# RF.net
KiCad netlist of a schematic drawn in Altium Designer
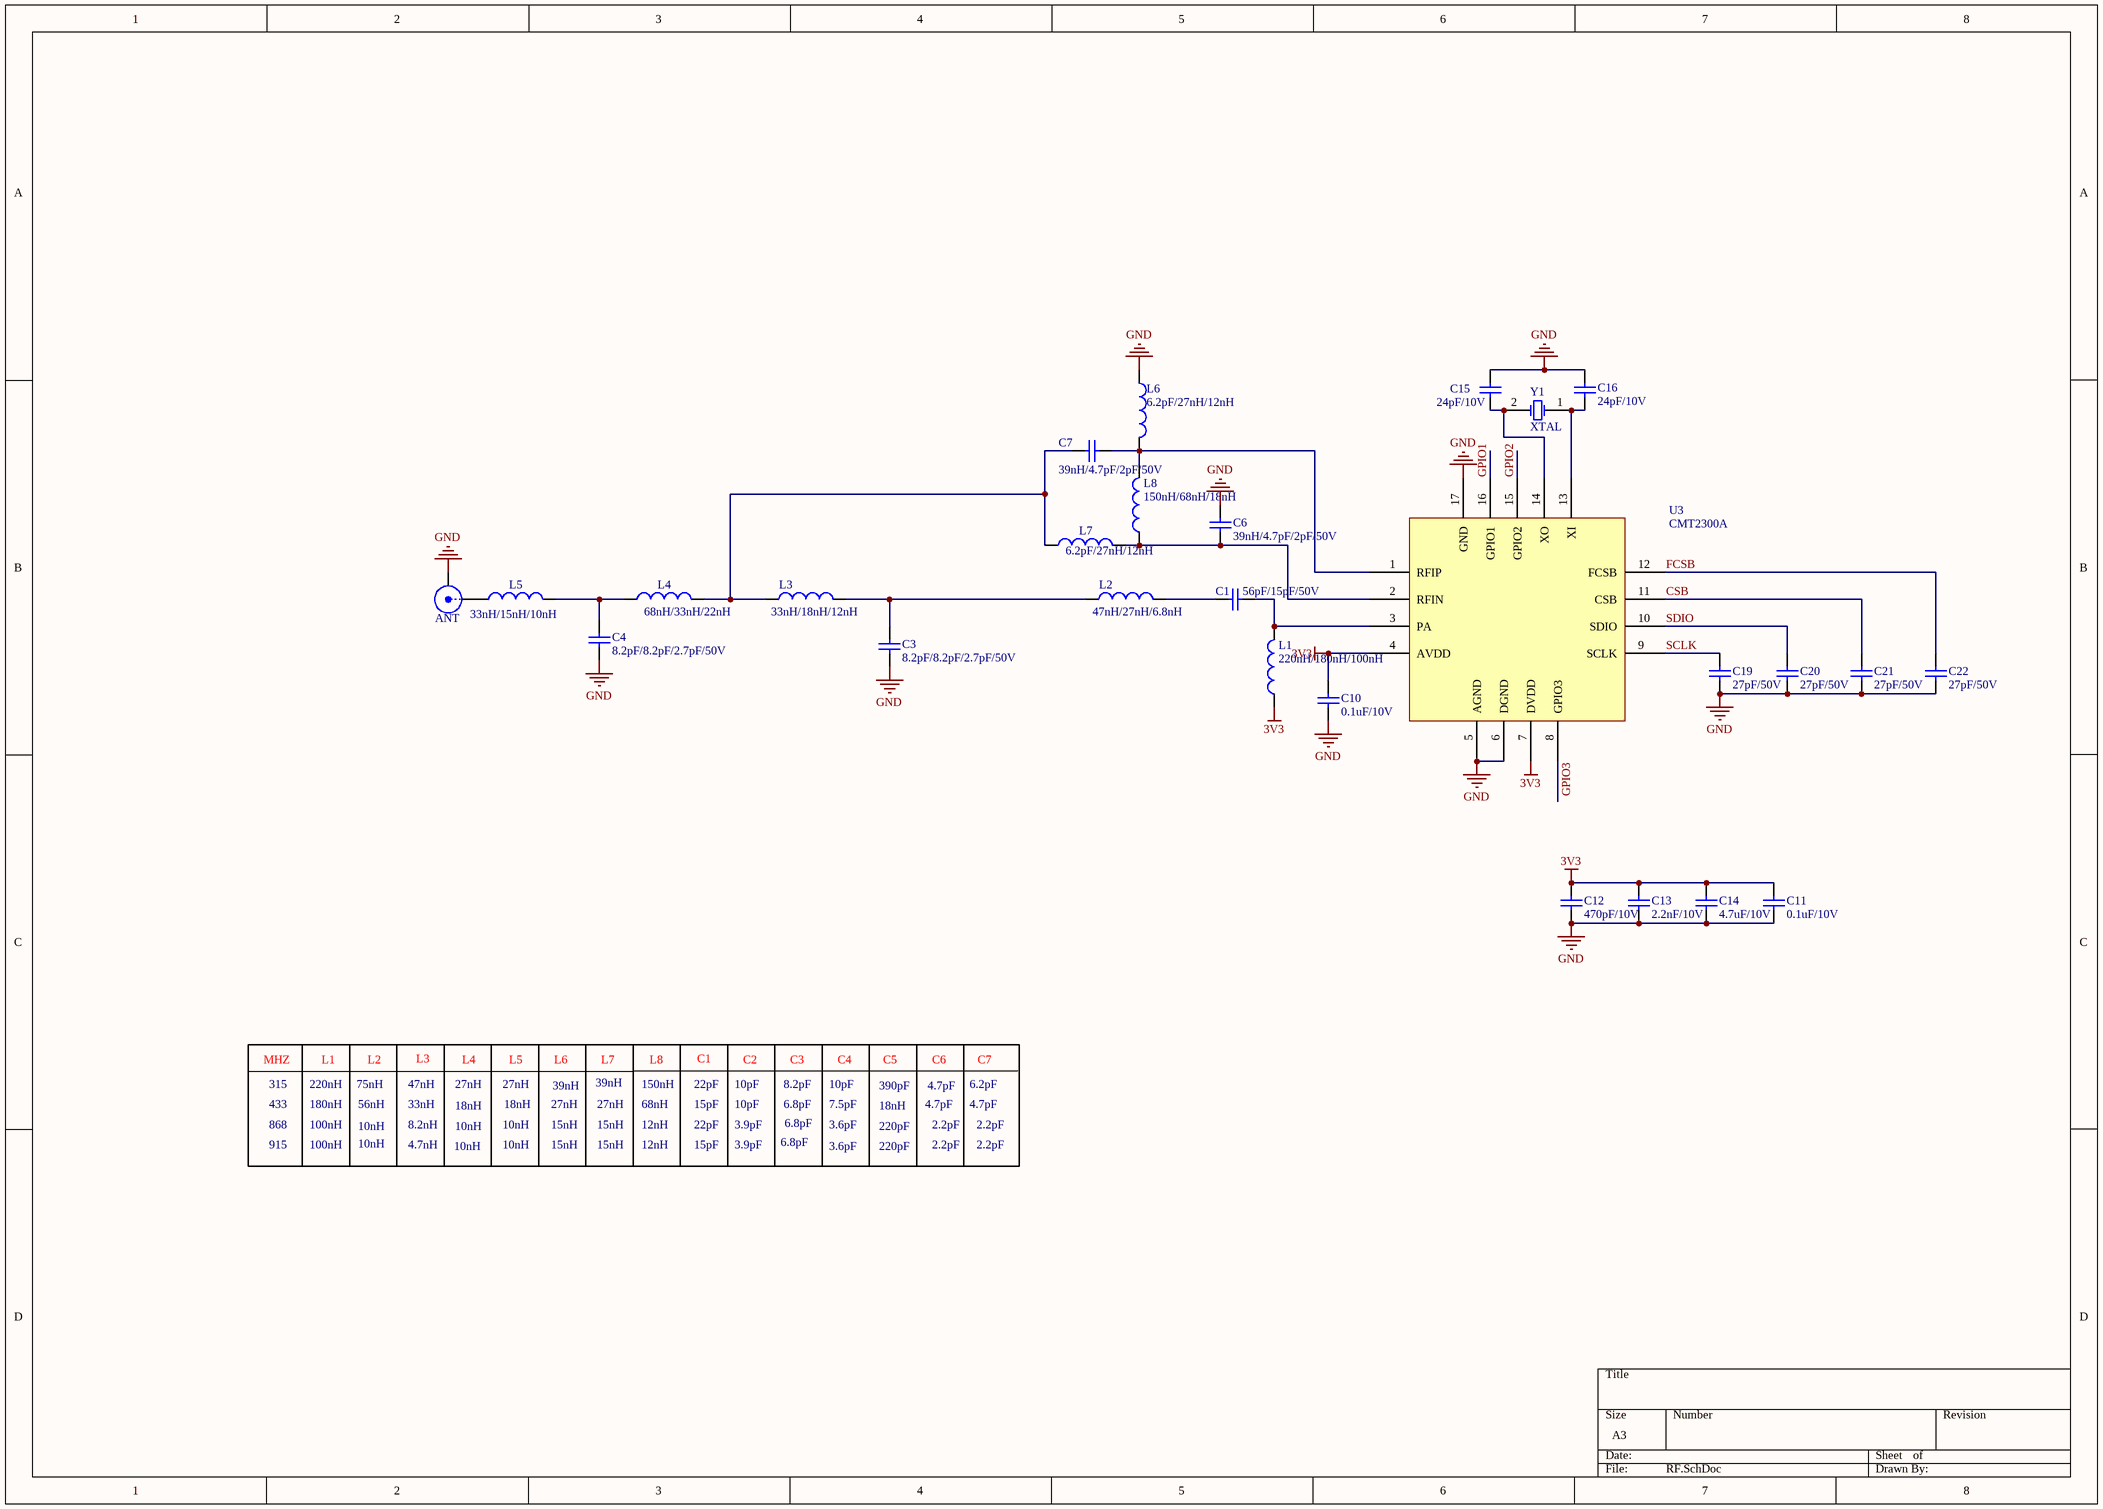
[diagram p0: RF.SchDoc]

(export (version "E")
  (design (tool "Eeschema 10.0.6"))
  (components
    (comp (ref "ANT")
      (value "~")
      (footprint "SMA Straight SMD")
      (description "SMA Straight Connector")
      (fields (field (name "PUBLISHER") "Altium Limited"))
      (libsource (lib "SX1276_e266v02a") (part "SMA"))
    )
    (comp (ref "C1")
      (value "56pF/15pF/50V")
      (footprint "0603C")
      (description "Capacitor")
      (fields (field (name "PUBLISHER") "Altium Limited"))
      (libsource (lib "Miscellaneous Devices") (part "Cap"))
    )
    (comp (ref "C3")
      (value "8.2pF/8.2pF/2.7pF/50V")
      (footprint "0603C")
      (description "Capacitor")
      (fields (field (name "PUBLISHER") "Altium Limited"))
      (libsource (lib "Miscellaneous Devices") (part "Cap"))
    )
    (comp (ref "C4")
      (value "8.2pF/8.2pF/2.7pF/50V")
      (footprint "0603C")
      (description "Capacitor")
      (fields (field (name "PUBLISHER") "Altium Limited"))
      (libsource (lib "Miscellaneous Devices") (part "Cap"))
    )
    (comp (ref "C6")
      (value "39nH/4.7pF/2pF/50V")
      (footprint "0603C")
      (description "Capacitor")
      (fields (field (name "PUBLISHER") "Altium Limited"))
      (libsource (lib "Miscellaneous Devices") (part "Cap"))
    )
    (comp (ref "C7")
      (value "39nH/4.7pF/2pF/50V")
      (footprint "0603C")
      (description "Capacitor")
      (fields (field (name "PUBLISHER") "Altium Limited"))
      (libsource (lib "Miscellaneous Devices") (part "Cap"))
    )
    (comp (ref "C10")
      (value "0.1uF/10V")
      (footprint "0603C")
      (description "Capacitor")
      (fields (field (name "PUBLISHER") "Altium Limited"))
      (libsource (lib "Miscellaneous Devices") (part "Cap"))
    )
    (comp (ref "C11")
      (value "0.1uF/10V")
      (footprint "0603C")
      (description "Capacitor")
      (fields (field (name "PUBLISHER") "Altium Limited"))
      (libsource (lib "Miscellaneous Devices") (part "Cap"))
    )
    (comp (ref "C12")
      (value "470pF/10V")
      (footprint "0603C")
      (description "Capacitor")
      (fields (field (name "PUBLISHER") "Altium Limited"))
      (libsource (lib "Miscellaneous Devices") (part "Cap"))
    )
    (comp (ref "C13")
      (value "2.2nF/10V")
      (footprint "0603C")
      (description "Capacitor")
      (fields (field (name "PUBLISHER") "Altium Limited"))
      (libsource (lib "Miscellaneous Devices") (part "Cap"))
    )
    (comp (ref "C14")
      (value "4.7uF/10V")
      (footprint "0603C")
      (description "Capacitor")
      (fields (field (name "PUBLISHER") "Altium Limited"))
      (libsource (lib "Miscellaneous Devices") (part "Cap"))
    )
    (comp (ref "C15")
      (value "24pF/10V")
      (footprint "0603C")
      (description "Capacitor")
      (fields (field (name "PUBLISHER") "Altium Limited"))
      (libsource (lib "Miscellaneous Devices") (part "Cap"))
    )
    (comp (ref "C16")
      (value "24pF/10V")
      (footprint "0603C")
      (description "Capacitor")
      (fields (field (name "PUBLISHER") "Altium Limited"))
      (libsource (lib "Miscellaneous Devices") (part "Cap"))
    )
    (comp (ref "C19")
      (value "27pF/50V")
      (footprint "0603C")
      (description "Capacitor")
      (fields (field (name "PUBLISHER") "Altium Limited"))
      (libsource (lib "Miscellaneous Devices") (part "Cap"))
    )
    (comp (ref "C20")
      (value "27pF/50V")
      (footprint "0603C")
      (description "Capacitor")
      (fields (field (name "PUBLISHER") "Altium Limited"))
      (libsource (lib "Miscellaneous Devices") (part "Cap"))
    )
    (comp (ref "C21")
      (value "27pF/50V")
      (footprint "0603C")
      (description "Capacitor")
      (fields (field (name "PUBLISHER") "Altium Limited"))
      (libsource (lib "Miscellaneous Devices") (part "Cap"))
    )
    (comp (ref "C22")
      (value "27pF/50V")
      (footprint "0603C")
      (description "Capacitor")
      (fields (field (name "PUBLISHER") "Altium Limited"))
      (libsource (lib "Miscellaneous Devices") (part "Cap"))
    )
    (comp (ref "L1")
      (value "220nH/180nH/100nH")
      (footprint "0603R")
      (description "Inductor")
      (fields (field (name "PUBLISHER") "Altium Limited"))
      (libsource (lib "Miscellaneous Devices") (part "Inductor"))
    )
    (comp (ref "L2")
      (value "47nH/27nH/6.8nH")
      (footprint "0603R")
      (description "Inductor")
      (fields (field (name "PUBLISHER") "Altium Limited"))
      (libsource (lib "Miscellaneous Devices") (part "Inductor"))
    )
    (comp (ref "L3")
      (value "33nH/18nH/12nH")
      (footprint "0603R")
      (description "Inductor")
      (fields (field (name "PUBLISHER") "Altium Limited"))
      (libsource (lib "Miscellaneous Devices") (part "Inductor"))
    )
    (comp (ref "L4")
      (value "68nH/33nH/22nH")
      (footprint "0603R")
      (description "Inductor")
      (fields (field (name "PUBLISHER") "Altium Limited"))
      (libsource (lib "Miscellaneous Devices") (part "Inductor"))
    )
    (comp (ref "L5")
      (value "33nH/15nH/10nH")
      (footprint "0603R")
      (description "Inductor")
      (fields (field (name "PUBLISHER") "Altium Limited"))
      (libsource (lib "Miscellaneous Devices") (part "Inductor"))
    )
    (comp (ref "L6")
      (value "6.2pF/27nH/12nH")
      (footprint "0603R")
      (description "Inductor")
      (fields (field (name "PUBLISHER") "Altium Limited"))
      (libsource (lib "Miscellaneous Devices") (part "Inductor"))
    )
    (comp (ref "L7")
      (value "6.2pF/27nH/12nH")
      (footprint "0603R")
      (description "Inductor")
      (fields (field (name "PUBLISHER") "Altium Limited"))
      (libsource (lib "Miscellaneous Devices") (part "Inductor"))
    )
    (comp (ref "L8")
      (value "150nH/68nH/18nH")
      (footprint "0603R")
      (description "Inductor")
      (fields (field (name "PUBLISHER") "Altium Limited"))
      (libsource (lib "Miscellaneous Devices") (part "Inductor"))
    )
    (comp (ref "U3") (value "CMT2300A") (libsource (lib "Schlib_20110825") (part "CMT2300A")))
    (comp (ref "Y1")
      (value "XTAL")
      (footprint "BCY-W2/D3.1")
      (description "Crystal Oscillator")
      (fields (field (name "PUBLISHER") "Altium Limited"))
      (libsource (lib "Miscellaneous Devices") (part "XTAL"))
    )
  )
  (nets
    (net (code "1") (name "/CSB") (class "Default")
      (node (ref "C21") (pin "1") (pinfunction "1_1") (pintype "passive"))
      (node (ref "U3") (pin "11") (pinfunction "CSB_11") (pintype "passive"))
    )
    (net (code "2") (name "/FCSB") (class "Default")
      (node (ref "C22") (pin "1") (pinfunction "1_1") (pintype "passive"))
      (node (ref "U3") (pin "12") (pinfunction "FCSB_12") (pintype "passive"))
    )
    (net (code "3") (name "/GPIO1") (class "Default")
      (node (ref "U3") (pin "16") (pinfunction "GPIO1_16") (pintype "passive"))
    )
    (net (code "4") (name "/GPIO2") (class "Default")
      (node (ref "U3") (pin "15") (pinfunction "GPIO2_15") (pintype "passive"))
    )
    (net (code "5") (name "/GPIO3") (class "Default")
      (node (ref "U3") (pin "8") (pinfunction "GPIO3_8") (pintype "passive"))
    )
    (net (code "6") (name "/SCLK") (class "Default")
      (node (ref "C19") (pin "1") (pinfunction "1_1") (pintype "passive"))
      (node (ref "U3") (pin "9") (pinfunction "SCLK_9") (pintype "passive"))
    )
    (net (code "7") (name "/SDIO") (class "Default")
      (node (ref "C20") (pin "1") (pinfunction "1_1") (pintype "passive"))
      (node (ref "U3") (pin "10") (pinfunction "SDIO_10") (pintype "passive"))
    )
    (net (code "8") (name "3V3") (class "Default")
      (node (ref "C10") (pin "1") (pinfunction "1_1") (pintype "passive"))
      (node (ref "C11") (pin "1") (pinfunction "1_1") (pintype "passive"))
      (node (ref "C12") (pin "1") (pinfunction "1_1") (pintype "passive"))
      (node (ref "C13") (pin "1") (pinfunction "1_1") (pintype "passive"))
      (node (ref "C14") (pin "1") (pinfunction "1_1") (pintype "passive"))
      (node (ref "L1") (pin "1") (pinfunction "1_1") (pintype "passive"))
      (node (ref "U3") (pin "4") (pinfunction "AVDD_4") (pintype "passive"))
      (node (ref "U3") (pin "7") (pinfunction "DVDD_7") (pintype "passive"))
    )
    (net (code "9") (name "GND") (class "Default")
      (node (ref "ANT") (pin "2") (pinfunction "GND_2") (pintype "passive"))
      (node (ref "C10") (pin "2") (pinfunction "2_2") (pintype "passive"))
      (node (ref "C11") (pin "2") (pinfunction "2_2") (pintype "passive"))
      (node (ref "C12") (pin "2") (pinfunction "2_2") (pintype "passive"))
      (node (ref "C13") (pin "2") (pinfunction "2_2") (pintype "passive"))
      (node (ref "C14") (pin "2") (pinfunction "2_2") (pintype "passive"))
      (node (ref "C15") (pin "1") (pinfunction "1_1") (pintype "passive"))
      (node (ref "C16") (pin "1") (pinfunction "1_1") (pintype "passive"))
      (node (ref "C19") (pin "2") (pinfunction "2_2") (pintype "passive"))
      (node (ref "C20") (pin "2") (pinfunction "2_2") (pintype "passive"))
      (node (ref "C21") (pin "2") (pinfunction "2_2") (pintype "passive"))
      (node (ref "C22") (pin "2") (pinfunction "2_2") (pintype "passive"))
      (node (ref "C3") (pin "2") (pinfunction "2_2") (pintype "passive"))
      (node (ref "C4") (pin "2") (pinfunction "2_2") (pintype "passive"))
      (node (ref "C6") (pin "2") (pinfunction "2_2") (pintype "passive"))
      (node (ref "L6") (pin "1") (pinfunction "1_1") (pintype "passive"))
      (node (ref "U3") (pin "17") (pinfunction "GND_17") (pintype "passive"))
      (node (ref "U3") (pin "5") (pinfunction "AGND_5") (pintype "passive"))
      (node (ref "U3") (pin "6") (pinfunction "DGND_6") (pintype "passive"))
    )
    (net (code "10") (name "Net-(ANT-Signal)") (class "Default")
      (node (ref "ANT") (pin "1") (pinfunction "Signal_1") (pintype "passive"))
      (node (ref "L5") (pin "1") (pinfunction "1_1") (pintype "passive"))
    )
    (net (code "11") (name "Net-(C1-Pad1)") (class "Default")
      (node (ref "C1") (pin "1") (pinfunction "1_1") (pintype "passive"))
      (node (ref "L2") (pin "2") (pinfunction "2_2") (pintype "passive"))
    )
    (net (code "12") (name "Net-(C3-Pad1)") (class "Default")
      (node (ref "C3") (pin "1") (pinfunction "1_1") (pintype "passive"))
      (node (ref "L2") (pin "1") (pinfunction "1_1") (pintype "passive"))
      (node (ref "L3") (pin "2") (pinfunction "2_2") (pintype "passive"))
    )
    (net (code "13") (name "Net-(C4-Pad1)") (class "Default")
      (node (ref "C4") (pin "1") (pinfunction "1_1") (pintype "passive"))
      (node (ref "L4") (pin "1") (pinfunction "1_1") (pintype "passive"))
      (node (ref "L5") (pin "2") (pinfunction "2_2") (pintype "passive"))
    )
    (net (code "14") (name "Net-(C7-Pad1)") (class "Default")
      (node (ref "C7") (pin "1") (pinfunction "1_1") (pintype "passive"))
      (node (ref "L3") (pin "1") (pinfunction "1_1") (pintype "passive"))
      (node (ref "L4") (pin "2") (pinfunction "2_2") (pintype "passive"))
      (node (ref "L7") (pin "1") (pinfunction "1_1") (pintype "passive"))
    )
    (net (code "15") (name "Net-(U3-PA)") (class "Default")
      (node (ref "C1") (pin "2") (pinfunction "2_2") (pintype "passive"))
      (node (ref "L1") (pin "2") (pinfunction "2_2") (pintype "passive"))
      (node (ref "U3") (pin "3") (pinfunction "PA_3") (pintype "passive"))
    )
    (net (code "16") (name "Net-(U3-RFIN)") (class "Default")
      (node (ref "C6") (pin "1") (pinfunction "1_1") (pintype "passive"))
      (node (ref "L7") (pin "2") (pinfunction "2_2") (pintype "passive"))
      (node (ref "L8") (pin "1") (pinfunction "1_1") (pintype "passive"))
      (node (ref "U3") (pin "2") (pinfunction "RFIN_2") (pintype "passive"))
    )
    (net (code "17") (name "Net-(U3-RFIP)") (class "Default")
      (node (ref "C7") (pin "2") (pinfunction "2_2") (pintype "passive"))
      (node (ref "L6") (pin "2") (pinfunction "2_2") (pintype "passive"))
      (node (ref "L8") (pin "2") (pinfunction "2_2") (pintype "passive"))
      (node (ref "U3") (pin "1") (pinfunction "RFIP_1") (pintype "passive"))
    )
    (net (code "18") (name "Net-(U3-XI)") (class "Default")
      (node (ref "C16") (pin "2") (pinfunction "2_2") (pintype "passive"))
      (node (ref "U3") (pin "13") (pinfunction "XI_13") (pintype "passive"))
      (node (ref "Y1") (pin "1") (pinfunction "OSC1_1") (pintype "passive"))
    )
    (net (code "19") (name "Net-(U3-XO)") (class "Default")
      (node (ref "C15") (pin "2") (pinfunction "2_2") (pintype "passive"))
      (node (ref "U3") (pin "14") (pinfunction "XO_14") (pintype "passive"))
      (node (ref "Y1") (pin "2") (pinfunction "OSC2_2") (pintype "passive"))
    )
  )
)
